# chip.net
KiCad netlist of a schematic drawn in Altium Designer
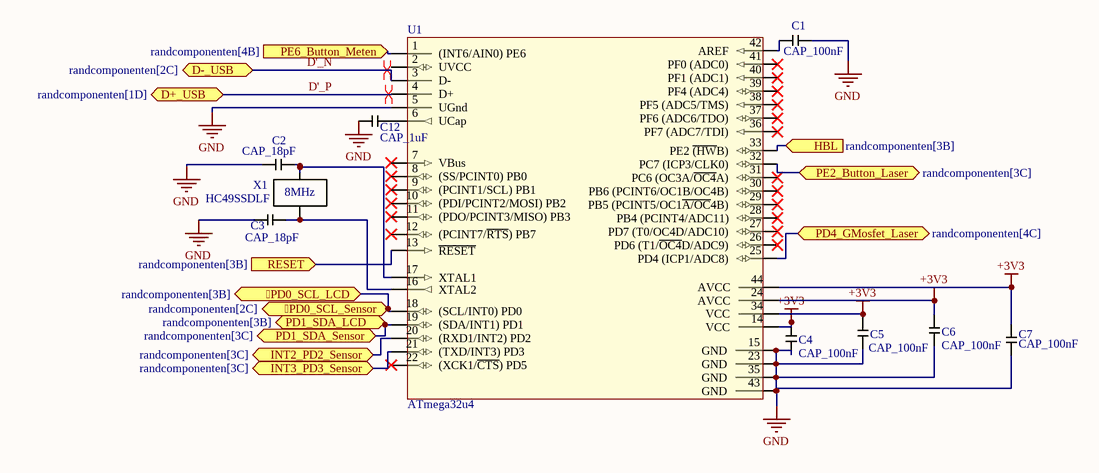
[diagram p0: chip.SchDoc]

(export (version "E")
  (design (tool "Eeschema 10.0.6"))
  (components
    (comp (ref "C1")
      (value "CAP_100nF")
      (footprint "CAP_100nF")
      (libsource (lib "CONDENSATOREN") (part "CAP_100nF"))
    )
    (comp (ref "C2")
      (value "CAP_18pF")
      (footprint "CAP_18pF")
      (libsource (lib "CONDENSATOREN") (part "CAP_18pF"))
    )
    (comp (ref "C3")
      (value "CAP_18pF")
      (footprint "CAP_18pF")
      (libsource (lib "CONDENSATOREN") (part "CAP_18pF"))
    )
    (comp (ref "C4")
      (value "CAP_100nF")
      (footprint "CAP_100nF")
      (libsource (lib "CONDENSATOREN") (part "CAP_100nF"))
    )
    (comp (ref "C5")
      (value "CAP_100nF")
      (footprint "CAP_100nF")
      (libsource (lib "CONDENSATOREN") (part "CAP_100nF"))
    )
    (comp (ref "C6")
      (value "CAP_100nF")
      (footprint "CAP_100nF")
      (libsource (lib "CONDENSATOREN") (part "CAP_100nF"))
    )
    (comp (ref "C7")
      (value "CAP_100nF")
      (footprint "CAP_100nF")
      (libsource (lib "CONDENSATOREN") (part "CAP_100nF"))
    )
    (comp (ref "C12")
      (value "CAP_1uF")
      (footprint "CAP_1uF")
      (libsource (lib "CONDENSATOREN") (part "CAP_1uF"))
    )
    (comp (ref "U1")
      (value "ATmega32u4")
      (footprint "Atmega32u4")
      (libsource (lib "BREIN") (part "ATmega32u4"))
    )
    (comp (ref "X1")
      (value "HC49SSDLF")
      (footprint "Xtal_HC49SSDLF")
      (libsource (lib "BREIN") (part "XTAL_8MHz"))
    )
  )
  (nets
    (net (code "1") (name "+3V3") (class "Default")
      (node (ref "C4") (pin "1") (pintype "passive"))
      (node (ref "C5") (pin "1") (pintype "passive"))
      (node (ref "C6") (pin "1") (pintype "passive"))
      (node (ref "C7") (pin "2") (pintype "passive"))
      (node (ref "U1") (pin "14") (pinfunction "VCC_14") (pintype "passive"))
      (node (ref "U1") (pin "24") (pinfunction "AVCC_24") (pintype "passive"))
      (node (ref "U1") (pin "34") (pinfunction "VCC_34") (pintype "passive"))
      (node (ref "U1") (pin "44") (pinfunction "AVCC_44") (pintype "passive"))
    )
    (net (code "2") (name "/PD0_SCL_LCD") (class "Default")
      (node (ref "U1") (pin "18") (pinfunction "(SCL/INT0)_PD0_18") (pintype "bidirectional"))
    )
    (net (code "3") (name "/D'_N") (class "Default")
      (node (ref "U1") (pin "3") (pinfunction "D-_3") (pintype "passive"))
    )
    (net (code "4") (name "/D'_P") (class "Default")
      (node (ref "U1") (pin "4") (pinfunction "D+_4") (pintype "passive"))
    )
    (net (code "5") (name "/HBL") (class "Default")
      (node (ref "U1") (pin "33") (pinfunction "PE2_~{(HW}B)_33") (pintype "bidirectional"))
    )
    (net (code "6") (name "/INT2_PD2_Sensor") (class "Default")
      (node (ref "U1") (pin "20") (pinfunction "(RXD1/INT2)_PD2_20") (pintype "bidirectional"))
    )
    (net (code "7") (name "/INT3_PD3_Sensor") (class "Default")
      (node (ref "U1") (pin "21") (pinfunction "(TXD/INT3)_PD3_21") (pintype "bidirectional"))
    )
    (net (code "8") (name "/PD1_SDA_LCD") (class "Default")
      (node (ref "U1") (pin "19") (pinfunction "(SDA/INT1)_PD1_19") (pintype "bidirectional"))
    )
    (net (code "9") (name "/PD4_GMosfet_Laser") (class "Default")
      (node (ref "U1") (pin "25") (pinfunction "PD4_(ICP1/ADC8)_25") (pintype "bidirectional"))
    )
    (net (code "10") (name "/PE2_Button_Laser") (class "Default")
      (node (ref "U1") (pin "32") (pinfunction "PC7_(ICP3/CLK0)_32") (pintype "bidirectional"))
    )
    (net (code "11") (name "/PE6_Button_Meten") (class "Default")
      (node (ref "U1") (pin "1") (pinfunction "(INT6/AIN0)_PE6_1") (pintype "passive"))
    )
    (net (code "12") (name "/RESET") (class "Default")
      (node (ref "U1") (pin "13") (pinfunction "~{RESET}_13") (pintype "input"))
    )
    (net (code "13") (name "GND") (class "Default")
      (node (ref "C1") (pin "2") (pintype "passive"))
      (node (ref "C12") (pin "1") (pintype "passive"))
      (node (ref "C2") (pin "2") (pintype "passive"))
      (node (ref "C3") (pin "2") (pintype "passive"))
      (node (ref "C4") (pin "2") (pintype "passive"))
      (node (ref "C5") (pin "2") (pintype "passive"))
      (node (ref "C6") (pin "2") (pintype "passive"))
      (node (ref "C7") (pin "1") (pintype "passive"))
      (node (ref "U1") (pin "15") (pinfunction "GND_15") (pintype "passive"))
      (node (ref "U1") (pin "23") (pinfunction "GND_23") (pintype "passive"))
      (node (ref "U1") (pin "35") (pinfunction "GND_35") (pintype "passive"))
      (node (ref "U1") (pin "43") (pinfunction "GND_43") (pintype "passive"))
      (node (ref "U1") (pin "5") (pinfunction "UGnd_5") (pintype "passive"))
    )
    (net (code "14") (name "Net-(U1-AREF)") (class "Default")
      (node (ref "C1") (pin "1") (pintype "passive"))
      (node (ref "U1") (pin "42") (pinfunction "AREF_42") (pintype "input"))
    )
    (net (code "15") (name "Net-(U1-UCap)") (class "Default")
      (node (ref "C12") (pin "2") (pintype "passive"))
      (node (ref "U1") (pin "6") (pinfunction "UCap_6") (pintype "output"))
    )
    (net (code "16") (name "Net-(U1-XTAL1)") (class "Default")
      (node (ref "C2") (pin "1") (pintype "passive"))
      (node (ref "U1") (pin "17") (pinfunction "XTAL1_17") (pintype "input"))
      (node (ref "X1") (pin "1") (pinfunction "Xtal_1_1") (pintype "passive"))
    )
    (net (code "17") (name "Net-(U1-XTAL2)") (class "Default")
      (node (ref "C3") (pin "1") (pintype "passive"))
      (node (ref "U1") (pin "16") (pinfunction "XTAL2_16") (pintype "output"))
      (node (ref "X1") (pin "2") (pinfunction "Xtal__2_2") (pintype "passive"))
    )
    (net (code "18") (name "unconnected-(U1-(PCINT1{slash}SCL)_PB1-Pad9)") (class "Default")
      (node (ref "U1") (pin "9") (pinfunction "(PCINT1/SCL)_PB1_9") (pintype "bidirectional+no_connect"))
    )
    (net (code "19") (name "unconnected-(U1-(PCINT7{slash}~{RTS})_PB7-Pad12)") (class "Default")
      (node (ref "U1") (pin "12") (pinfunction "(PCINT7/~{RTS})_PB7_12") (pintype "bidirectional+no_connect"))
    )
    (net (code "20") (name "unconnected-(U1-(PDI{slash}PCINT2{slash}MOSI)_PB2-Pad10)") (class "Default")
      (node (ref "U1") (pin "10") (pinfunction "(PDI/PCINT2/MOSI)_PB2_10") (pintype "bidirectional+no_connect"))
    )
    (net (code "21") (name "unconnected-(U1-(PDO{slash}PCINT3{slash}MISO)_PB3-Pad11)") (class "Default")
      (node (ref "U1") (pin "11") (pinfunction "(PDO/PCINT3/MISO)_PB3_11") (pintype "bidirectional+no_connect"))
    )
    (net (code "22") (name "unconnected-(U1-(SS{slash}PCINT0)_PB0-Pad8)") (class "Default")
      (node (ref "U1") (pin "8") (pinfunction "(SS/PCINT0)_PB0_8") (pintype "bidirectional+no_connect"))
    )
    (net (code "23") (name "unconnected-(U1-(XCK1{slash}~{CTS})_PD5-Pad22)") (class "Default")
      (node (ref "U1") (pin "22") (pinfunction "(XCK1/~{CTS})_PD5_22") (pintype "bidirectional+no_connect"))
    )
    (net (code "24") (name "unconnected-(U1-PB4_(PCINT4{slash}ADC11)-Pad28)") (class "Default")
      (node (ref "U1") (pin "28") (pinfunction "PB4_(PCINT4/ADC11)_28") (pintype "bidirectional+no_connect"))
    )
    (net (code "25") (name "unconnected-(U1-PB5_(PCINT5{slash}OC1~{A{slash}OC}4B)-Pad29)") (class "Default")
      (node (ref "U1") (pin "29") (pinfunction "PB5_(PCINT5/OC1~{A/OC}4B)_29") (pintype "bidirectional+no_connect"))
    )
    (net (code "26") (name "unconnected-(U1-PB6_(PCINT6{slash}OC1B{slash}OC4B)-Pad30)") (class "Default")
      (node (ref "U1") (pin "30") (pinfunction "PB6_(PCINT6/OC1B/OC4B)_30") (pintype "bidirectional+no_connect"))
    )
    (net (code "27") (name "unconnected-(U1-PC6_(OC3A{slash}~{OC4}A)-Pad31)") (class "Default")
      (node (ref "U1") (pin "31") (pinfunction "PC6_(OC3A/~{OC4}A)_31") (pintype "bidirectional+no_connect"))
    )
    (net (code "28") (name "unconnected-(U1-PD6_(T1{slash}~{OC4}D{slash}ADC9)-Pad26)") (class "Default")
      (node (ref "U1") (pin "26") (pinfunction "PD6_(T1/~{OC4}D/ADC9)_26") (pintype "bidirectional+no_connect"))
    )
    (net (code "29") (name "unconnected-(U1-PD7_(T0{slash}OC4D{slash}ADC10)-Pad27)") (class "Default")
      (node (ref "U1") (pin "27") (pinfunction "PD7_(T0/OC4D/ADC10)_27") (pintype "bidirectional+no_connect"))
    )
    (net (code "30") (name "unconnected-(U1-PF0_(ADC0)-Pad41)") (class "Default")
      (node (ref "U1") (pin "41") (pinfunction "PF0_(ADC0)_41") (pintype "input+no_connect"))
    )
    (net (code "31") (name "unconnected-(U1-PF1_(ADC1)-Pad40)") (class "Default")
      (node (ref "U1") (pin "40") (pinfunction "PF1_(ADC1)_40") (pintype "input+no_connect"))
    )
    (net (code "32") (name "unconnected-(U1-PF4_(ADC4)-Pad39)") (class "Default")
      (node (ref "U1") (pin "39") (pinfunction "PF4_(ADC4)_39") (pintype "bidirectional+no_connect"))
    )
    (net (code "33") (name "unconnected-(U1-PF5_(ADC5{slash}TMS)-Pad38)") (class "Default")
      (node (ref "U1") (pin "38") (pinfunction "PF5_(ADC5/TMS)_38") (pintype "input+no_connect"))
    )
    (net (code "34") (name "unconnected-(U1-PF6_(ADC6{slash}TDO)-Pad37)") (class "Default")
      (node (ref "U1") (pin "37") (pinfunction "PF6_(ADC6/TDO)_37") (pintype "bidirectional+no_connect"))
    )
    (net (code "35") (name "unconnected-(U1-PF7_(ADC7{slash}TDI)-Pad36)") (class "Default")
      (node (ref "U1") (pin "36") (pinfunction "PF7_(ADC7/TDI)_36") (pintype "input+no_connect"))
    )
    (net (code "36") (name "unconnected-(U1-UVCC-Pad2)") (class "Default")
      (node (ref "U1") (pin "2") (pinfunction "UVCC_2") (pintype "bidirectional"))
    )
    (net (code "37") (name "unconnected-(U1-VBus-Pad7)") (class "Default")
      (node (ref "U1") (pin "7") (pinfunction "VBus_7") (pintype "input+no_connect"))
    )
  )
)
